# Power.net
KiCad netlist of a schematic drawn in Altium Designer
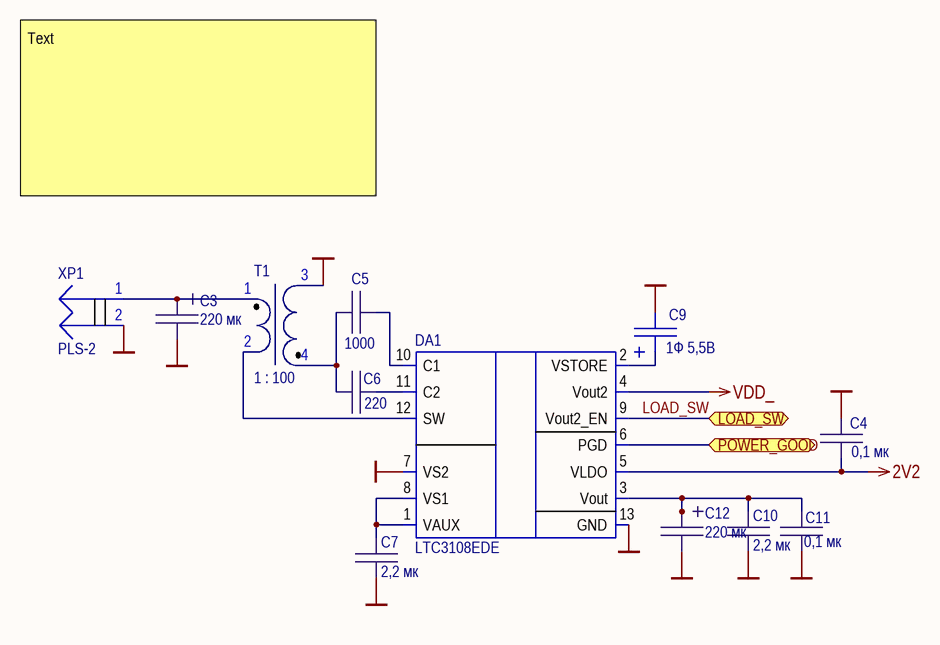
[diagram p0: Power.SchDoc]

(export (version "E")
  (design (tool "Eeschema 10.0.6"))
  (components
    (comp (ref "C3")
      (value "220 мк")
      (footprint "B_CASE")
      (description "CAP TANT 220UF 10% 2.5V 1411")
      (fields (field (name "PART NUMBER") "TAJB227K002RNJ") (field (name "MANUFACTURER") "AVX Corporation"))
      (libsource (lib "Database_Lib") (part "Tantalum Capacitor"))
    )
    (comp (ref "C4")
      (value "0,1 мк")
      (footprint "C_0603")
      (description "CAP CER 0.1UF 100V X7R 0603")
      (fields
        (field (name "PART NUMBER") "GRM188R72A104MA35D")
        (field (name "MANUFACTURER") "Murata Electronics")
      )
      (libsource (lib "Database_Lib") (part "Capasitor"))
    )
    (comp (ref "C5")
      (value "1000")
      (footprint "C_0603")
      (description "CAP CER 1000PF 50V C0G/NP0 0603")
      (fields
        (field (name "PART NUMBER") "GRM1885C1H102FA01J")
        (field (name "MANUFACTURER") "Murata Electronics")
      )
      (libsource (lib "Database_Lib") (part "Capasitor"))
    )
    (comp (ref "C6")
      (value "220")
      (footprint "C_0603")
      (description "CAP CER 220PF 100V C0G/NP0 0603")
      (fields
        (field (name "PART NUMBER") "GRM1885C2A221FA01D")
        (field (name "MANUFACTURER") "Murata Electronics")
      )
      (libsource (lib "Database_Lib") (part "Capasitor"))
    )
    (comp (ref "C7")
      (value "2,2 мк")
      (footprint "C_0603")
      (description "CAP CER 2.2UF 25V X5R 0603")
      (fields
        (field (name "PART NUMBER") "GRM188R61E225MA12D")
        (field (name "MANUFACTURER") "Murata Electronics")
      )
      (libsource (lib "Database_Lib") (part "Capasitor"))
    )
    (comp (ref "C9")
      (value "1Ф 5,5В")
      (footprint "EECF5R5u")
      (description "1 Ф, 5.5 В, 5 мм, 2208H, Ионистор")
      (libsource (lib "2.Capasitors") (part "EECF5R5U105"))
    )
    (comp (ref "C10")
      (value "2,2 мк")
      (footprint "C_0603")
      (description "CAP CER 2.2UF 25V X5R 0603")
      (fields
        (field (name "PART NUMBER") "GRM188R61E225MA12D")
        (field (name "MANUFACTURER") "Murata Electronics")
      )
      (libsource (lib "Database_Lib") (part "Capasitor"))
    )
    (comp (ref "C11")
      (value "0,1 мк")
      (footprint "C_0603")
      (description "CAP CER 0.1UF 100V X7R 0603")
      (fields
        (field (name "PART NUMBER") "GRM188R72A104MA35D")
        (field (name "MANUFACTURER") "Murata Electronics")
      )
      (libsource (lib "Database_Lib") (part "Capasitor"))
    )
    (comp (ref "C12")
      (value "220 мк")
      (footprint "B_CASE")
      (description "CAP TANT 220UF 10% 2.5V 1411")
      (fields (field (name "PART NUMBER") "TAJB227K002RNJ") (field (name "MANUFACTURER") "AVX Corporation"))
      (libsource (lib "Database_Lib") (part "Tantalum Capacitor"))
    )
    (comp (ref "DA1")
      (value "LTC3108EDE")
      (footprint "DFN-12")
      (description "Ultralow Voltage Step-Up Converter and Power Manager")
      (libsource (lib "6.Chips") (part "LTC3108EDE"))
    )
    (comp (ref "T1")
      (value "1 : 100")
      (footprint "LPR6235")
      (description "Coupled Inductor")
      (libsource (lib "13.Transformers") (part "LPR6235-752SMR"))
    )
    (comp (ref "XP1") (value "PLS-2") (footprint "PLS-2") (libsource (lib "7.Connectors") (part "PLS-2")))
  )
  (nets
    (net (code "1") (name "/LOAD_SW") (class "Default")
      (node (ref "DA1") (pin "9") (pinfunction "Vout2_EN_9") (pintype "passive"))
    )
    (net (code "2") (name "/POWER_GOOD") (class "Default")
      (node (ref "DA1") (pin "6") (pinfunction "PGD_6") (pintype "passive"))
    )
    (net (code "3") (name "2V2") (class "Default")
      (node (ref "C4") (pin "2") (pinfunction "2_2") (pintype "passive"))
      (node (ref "DA1") (pin "5") (pinfunction "VLDO_5") (pintype "passive"))
    )
    (net (code "4") (name "GND") (class "Default")
      (node (ref "C10") (pin "1") (pinfunction "1_1") (pintype "passive"))
      (node (ref "C11") (pin "1") (pinfunction "1_1") (pintype "passive"))
      (node (ref "C12") (pin "2") (pinfunction "2_2") (pintype "passive"))
      (node (ref "C3") (pin "2") (pinfunction "2_2") (pintype "passive"))
      (node (ref "C4") (pin "1") (pinfunction "1_1") (pintype "passive"))
      (node (ref "C7") (pin "1") (pinfunction "1_1") (pintype "passive"))
      (node (ref "C9") (pin "2") (pinfunction "2_2") (pintype "passive"))
      (node (ref "DA1") (pin "13") (pinfunction "GND_13") (pintype "passive"))
      (node (ref "DA1") (pin "7") (pinfunction "VS2_7") (pintype "passive"))
      (node (ref "T1") (pin "3") (pinfunction "3_3") (pintype "passive"))
      (node (ref "XP1") (pin "2") (pinfunction "2_2") (pintype "passive"))
    )
    (net (code "5") (name "Net-(C3-Pad1)") (class "Default")
      (node (ref "C3") (pin "1") (pinfunction "1_1") (pintype "passive"))
      (node (ref "T1") (pin "1") (pinfunction "1_1") (pintype "passive"))
      (node (ref "XP1") (pin "1") (pinfunction "1_1") (pintype "passive"))
    )
    (net (code "6") (name "Net-(C5-Pad1)") (class "Default")
      (node (ref "C5") (pin "1") (pinfunction "1_1") (pintype "passive"))
      (node (ref "C6") (pin "1") (pinfunction "1_1") (pintype "passive"))
      (node (ref "T1") (pin "4") (pinfunction "4_4") (pintype "passive"))
    )
    (net (code "7") (name "Net-(DA1-C1)") (class "Default")
      (node (ref "C5") (pin "2") (pinfunction "2_2") (pintype "passive"))
      (node (ref "DA1") (pin "10") (pinfunction "C1_10") (pintype "passive"))
    )
    (net (code "8") (name "Net-(DA1-C2)") (class "Default")
      (node (ref "C6") (pin "2") (pinfunction "2_2") (pintype "passive"))
      (node (ref "DA1") (pin "11") (pinfunction "C2_11") (pintype "passive"))
    )
    (net (code "9") (name "Net-(DA1-SW)") (class "Default")
      (node (ref "DA1") (pin "12") (pinfunction "SW_12") (pintype "passive"))
      (node (ref "T1") (pin "2") (pinfunction "2_2") (pintype "passive"))
    )
    (net (code "10") (name "Net-(DA1-VAUX)") (class "Default")
      (node (ref "C7") (pin "2") (pinfunction "2_2") (pintype "passive"))
      (node (ref "DA1") (pin "1") (pinfunction "VAUX_1") (pintype "passive"))
      (node (ref "DA1") (pin "8") (pinfunction "VS1_8") (pintype "passive"))
    )
    (net (code "11") (name "Net-(DA1-VSTORE)") (class "Default")
      (node (ref "C9") (pin "1") (pinfunction "1_1") (pintype "passive"))
      (node (ref "DA1") (pin "2") (pinfunction "VSTORE_2") (pintype "passive"))
    )
    (net (code "12") (name "Net-(DA1-Vout)") (class "Default")
      (node (ref "C10") (pin "2") (pinfunction "2_2") (pintype "passive"))
      (node (ref "C11") (pin "2") (pinfunction "2_2") (pintype "passive"))
      (node (ref "C12") (pin "1") (pinfunction "1_1") (pintype "passive"))
      (node (ref "DA1") (pin "3") (pinfunction "Vout_3") (pintype "passive"))
    )
    (net (code "13") (name "VDD_") (class "Default")
      (node (ref "DA1") (pin "4") (pinfunction "Vout2_4") (pintype "passive"))
    )
  )
)
